# Teilentwurf.net
KiCad netlist of a schematic drawn in EAGLE
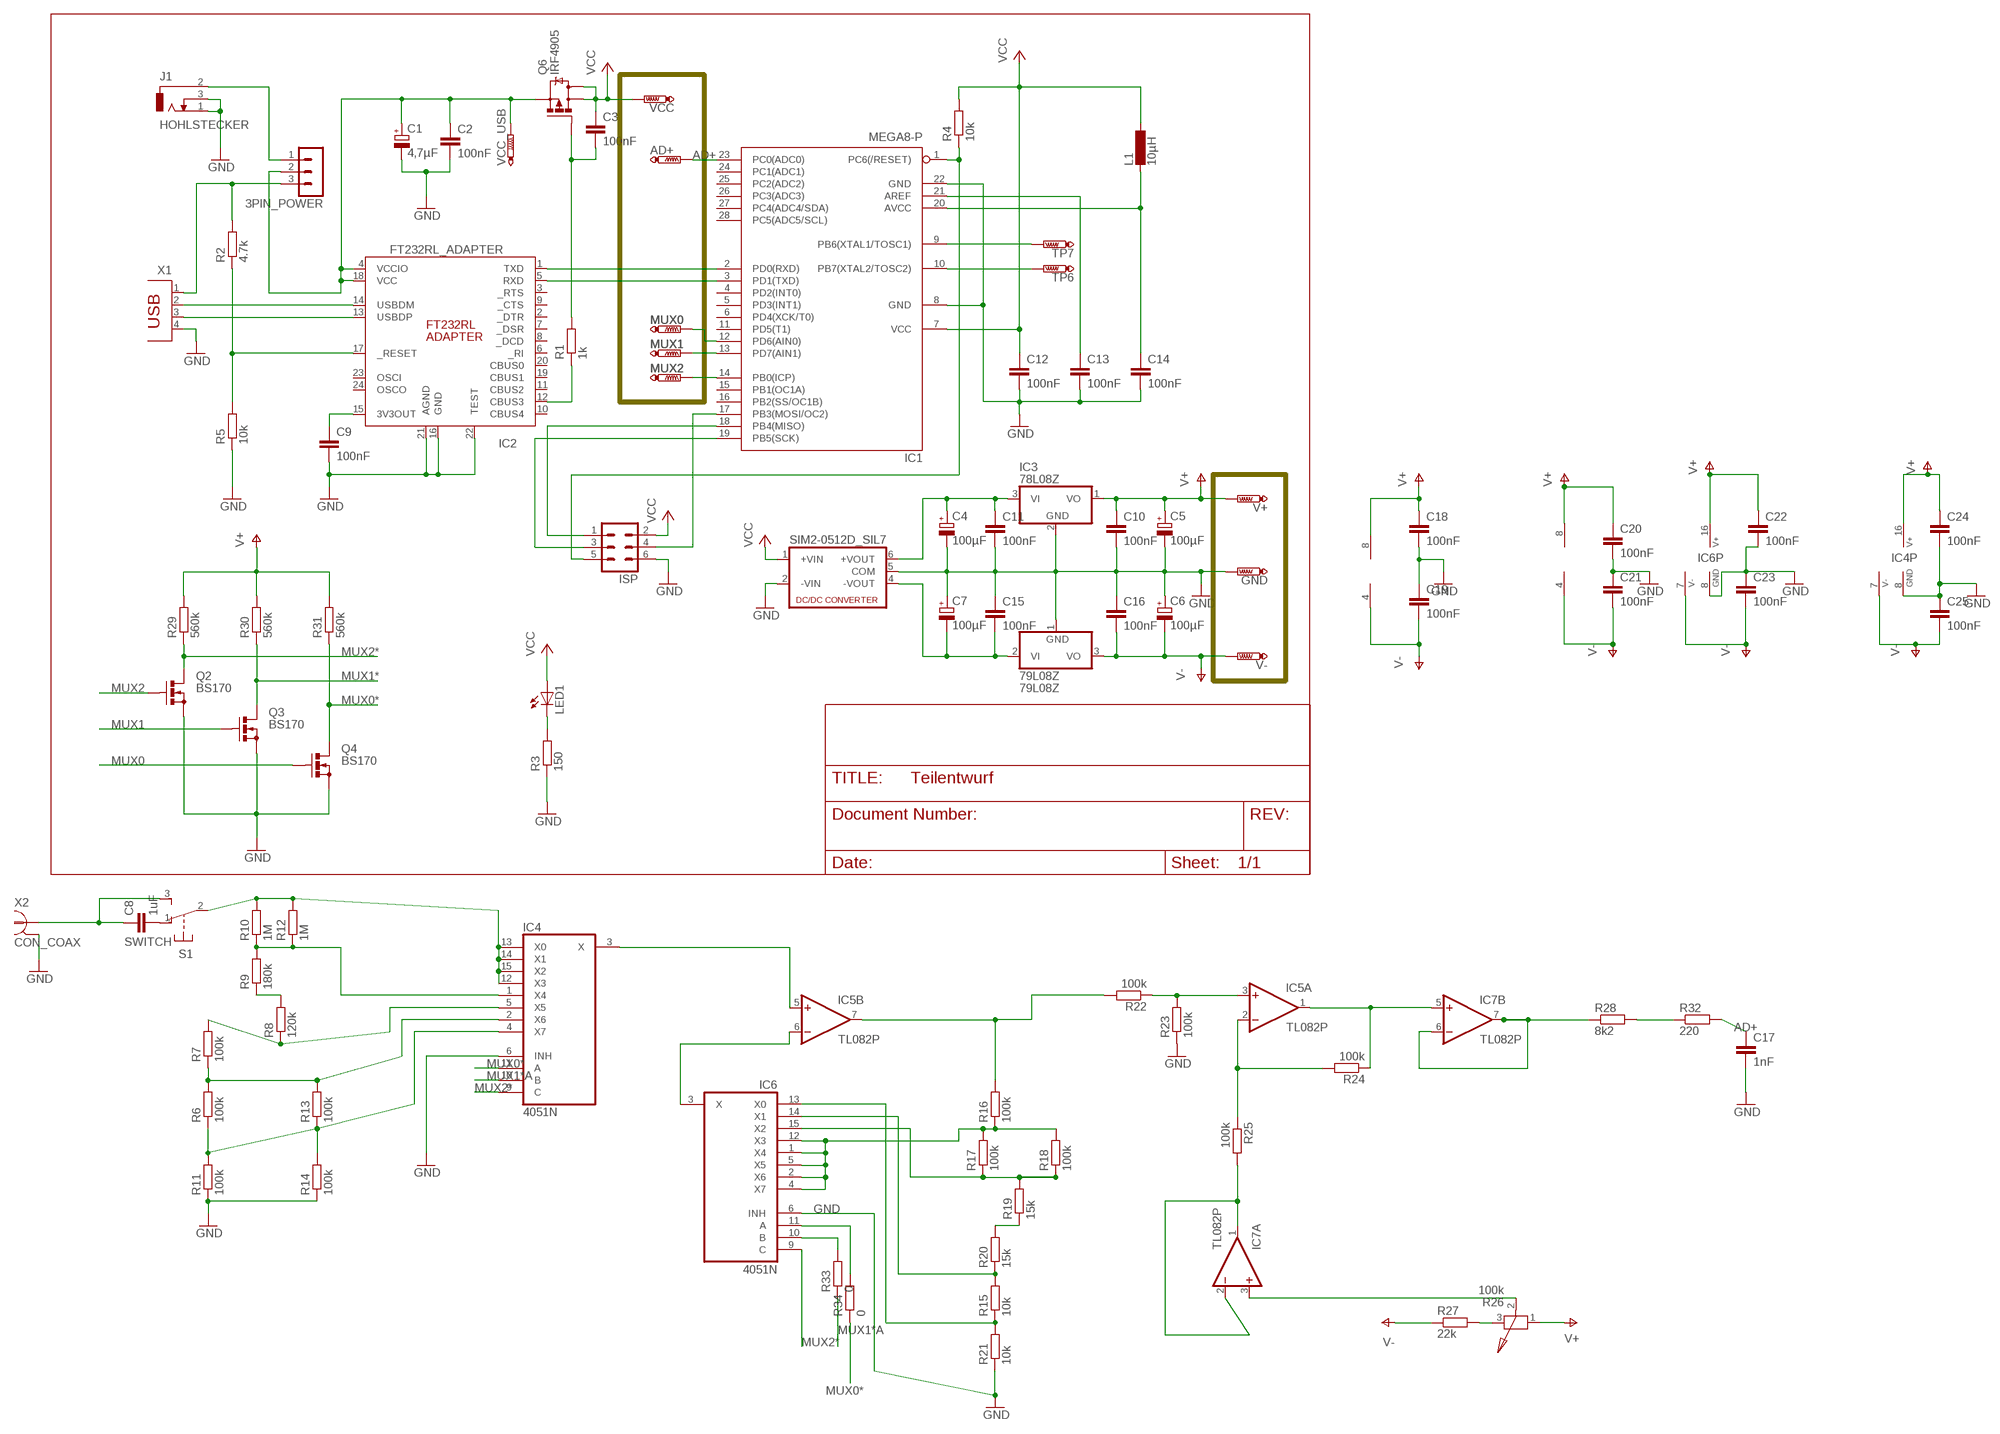
[diagram p0: schematic, sheet 1]

(export (version "E")
  (design (tool "Eeschema 10.0.6"))
  (components
    (comp (ref "3PIN_POWER")
      (value "MA03-1")
      (footprint "eagle-import:MA03-1")
      (libsource (lib "eagle-import") (part "MA03-1"))
    )
    (comp (ref "79L08Z")
      (value "79L08Z")
      (footprint "eagle-import:TO92")
      (libsource (lib "eagle-import") (part "79ZL08"))
    )
    (comp (ref "AD+")
      (value "PTR1PAD1-13Y")
      (footprint "eagle-import:P1-13Y")
      (libsource (lib "eagle-import") (part "PTR1PAD1-13Y"))
    )
    (comp (ref "C1")
      (value "4,7µF")
      (footprint "eagle-import:E2-5")
      (libsource (lib "eagle-import") (part "CPOL-EUE2-5"))
    )
    (comp (ref "C2")
      (value "100nF")
      (footprint "eagle-import:C025-030X050")
      (libsource (lib "eagle-import") (part "C-EU025-030X050"))
    )
    (comp (ref "C3")
      (value "100nF")
      (footprint "eagle-import:C025-030X050")
      (libsource (lib "eagle-import") (part "C-EU025-030X050"))
    )
    (comp (ref "C4")
      (value "100µF")
      (footprint "eagle-import:E2,5-7")
      (libsource (lib "eagle-import") (part "CPOL-EUE2.5-7"))
    )
    (comp (ref "C5")
      (value "100µF")
      (footprint "eagle-import:E2,5-7")
      (libsource (lib "eagle-import") (part "CPOL-EUE2.5-7"))
    )
    (comp (ref "C6")
      (value "100µF")
      (footprint "eagle-import:E2,5-7")
      (libsource (lib "eagle-import") (part "CPOL-EUE2.5-7"))
    )
    (comp (ref "C7")
      (value "100µF")
      (footprint "eagle-import:E2,5-7")
      (libsource (lib "eagle-import") (part "CPOL-EUE2.5-7"))
    )
    (comp (ref "C8")
      (value "1uF")
      (footprint "eagle-import:C050-050X075")
      (libsource (lib "eagle-import") (part "C-EU050-050X075"))
    )
    (comp (ref "C9")
      (value "100nF")
      (footprint "eagle-import:C025-030X050")
      (libsource (lib "eagle-import") (part "C-EU025-030X050"))
    )
    (comp (ref "C10")
      (value "100nF")
      (footprint "eagle-import:C025-030X050")
      (libsource (lib "eagle-import") (part "C-EU025-030X050"))
    )
    (comp (ref "C11")
      (value "100nF")
      (footprint "eagle-import:C025-030X050")
      (libsource (lib "eagle-import") (part "C-EU025-030X050"))
    )
    (comp (ref "C12")
      (value "100nF")
      (footprint "eagle-import:C025-030X050")
      (libsource (lib "eagle-import") (part "C-EU025-030X050"))
    )
    (comp (ref "C13")
      (value "100nF")
      (footprint "eagle-import:C025-030X050")
      (libsource (lib "eagle-import") (part "C-EU025-030X050"))
    )
    (comp (ref "C14")
      (value "100nF")
      (footprint "eagle-import:C025-030X050")
      (libsource (lib "eagle-import") (part "C-EU025-030X050"))
    )
    (comp (ref "C15")
      (value "100nF")
      (footprint "eagle-import:C025-030X050")
      (libsource (lib "eagle-import") (part "C-EU025-030X050"))
    )
    (comp (ref "C16")
      (value "100nF")
      (footprint "eagle-import:C025-030X050")
      (libsource (lib "eagle-import") (part "C-EU025-030X050"))
    )
    (comp (ref "C17")
      (value "1nF")
      (footprint "eagle-import:C025-030X050")
      (libsource (lib "eagle-import") (part "C-EU025-030X050"))
    )
    (comp (ref "C18")
      (value "100nF")
      (footprint "eagle-import:C025-030X050")
      (libsource (lib "eagle-import") (part "C-EU025-030X050"))
    )
    (comp (ref "C19")
      (value "100nF")
      (footprint "eagle-import:C025-030X050")
      (libsource (lib "eagle-import") (part "C-EU025-030X050"))
    )
    (comp (ref "C20")
      (value "100nF")
      (footprint "eagle-import:C025-030X050")
      (libsource (lib "eagle-import") (part "C-EU025-030X050"))
    )
    (comp (ref "C21")
      (value "100nF")
      (footprint "eagle-import:C025-030X050")
      (libsource (lib "eagle-import") (part "C-EU025-030X050"))
    )
    (comp (ref "C22")
      (value "100nF")
      (footprint "eagle-import:C025-030X050")
      (libsource (lib "eagle-import") (part "C-EU025-030X050"))
    )
    (comp (ref "C23")
      (value "100nF")
      (footprint "eagle-import:C025-030X050")
      (libsource (lib "eagle-import") (part "C-EU025-030X050"))
    )
    (comp (ref "C24")
      (value "100nF")
      (footprint "eagle-import:C025-030X050")
      (libsource (lib "eagle-import") (part "C-EU025-030X050"))
    )
    (comp (ref "C25")
      (value "100nF")
      (footprint "eagle-import:C025-030X050")
      (libsource (lib "eagle-import") (part "C-EU025-030X050"))
    )
    (comp (ref "GND")
      (value "PTR1PAD1-13Y")
      (footprint "eagle-import:P1-13Y")
      (libsource (lib "eagle-import") (part "PTR1PAD1-13Y"))
    )
    (comp (ref "IC1")
      (value "MEGA8-P")
      (footprint "eagle-import:DIL28-3")
      (libsource (lib "eagle-import") (part "MEGA8-P"))
    )
    (comp (ref "IC2")
      (value "FT232RL_ADAPTER")
      (footprint "eagle-import:DIL24-9")
      (libsource (lib "eagle-import") (part "FT232RL_ADAPTER"))
    )
    (comp (ref "IC3")
      (value "78L08Z")
      (footprint "eagle-import:TO92")
      (libsource (lib "eagle-import") (part "78ZL08"))
    )
    (comp (ref "IC4")
      (value "4051N")
      (footprint "eagle-import:DIL16")
      (libsource (lib "eagle-import") (part "4051N"))
    )
    (comp (ref "IC5")
      (value "TL082P")
      (footprint "eagle-import:DIL08")
      (libsource (lib "eagle-import") (part "TL082P"))
    )
    (comp (ref "IC6")
      (value "4051N")
      (footprint "eagle-import:DIL16")
      (libsource (lib "eagle-import") (part "4051N"))
    )
    (comp (ref "IC7")
      (value "TL082P")
      (footprint "eagle-import:DIL08")
      (libsource (lib "eagle-import") (part "TL082P"))
    )
    (comp (ref "ISP")
      (value "ML6")
      (footprint "eagle-import:ML6")
      (libsource (lib "eagle-import") (part "ML6"))
    )
    (comp (ref "J1")
      (value "HOHLSTECKER")
      (footprint "eagle-import:HOHLSTECKER_25")
      (libsource (lib "eagle-import") (part "HOHLSTECKER"))
    )
    (comp (ref "L1")
      (value "10µH")
      (footprint "eagle-import:0207_12")
      (libsource (lib "eagle-import") (part "L-EU0207/12"))
    )
    (comp (ref "LED1")
      (value "LED3MM")
      (footprint "eagle-import:LED3MM")
      (libsource (lib "eagle-import") (part "LED3MM"))
    )
    (comp (ref "MUX0")
      (value "PTR1PAD1-13Y")
      (footprint "eagle-import:P1-13Y")
      (libsource (lib "eagle-import") (part "PTR1PAD1-13Y"))
    )
    (comp (ref "MUX1")
      (value "PTR1PAD1-13Y")
      (footprint "eagle-import:P1-13Y")
      (libsource (lib "eagle-import") (part "PTR1PAD1-13Y"))
    )
    (comp (ref "MUX2")
      (value "PTR1PAD1-13Y")
      (footprint "eagle-import:P1-13Y")
      (libsource (lib "eagle-import") (part "PTR1PAD1-13Y"))
    )
    (comp (ref "Q2")
      (value "BS170")
      (footprint "eagle-import:SOT54E")
      (libsource (lib "eagle-import") (part "BS170"))
    )
    (comp (ref "Q3")
      (value "BS170")
      (footprint "eagle-import:SOT54E")
      (libsource (lib "eagle-import") (part "BS170"))
    )
    (comp (ref "Q4")
      (value "BS170")
      (footprint "eagle-import:SOT54E")
      (libsource (lib "eagle-import") (part "BS170"))
    )
    (comp (ref "Q6")
      (value "IRF4905")
      (footprint "eagle-import:TO220PAD")
      (libsource (lib "eagle-import") (part "IRF4905PBF"))
    )
    (comp (ref "R1")
      (value "1k")
      (footprint "eagle-import:0207_10")
      (libsource (lib "eagle-import") (part "R-EU_0207/10"))
    )
    (comp (ref "R2")
      (value "4.7k")
      (footprint "eagle-import:0207_10")
      (libsource (lib "eagle-import") (part "R-EU_0207/10"))
    )
    (comp (ref "R3")
      (value "150")
      (footprint "eagle-import:0207_10")
      (libsource (lib "eagle-import") (part "R-EU_0207/10"))
    )
    (comp (ref "R4")
      (value "10k")
      (footprint "eagle-import:0207_12")
      (libsource (lib "eagle-import") (part "R-EU_0207/12"))
    )
    (comp (ref "R5")
      (value "10k")
      (footprint "eagle-import:0207_10")
      (libsource (lib "eagle-import") (part "R-EU_0207/10"))
    )
    (comp (ref "R6")
      (value "100k")
      (footprint "eagle-import:0207_10")
      (libsource (lib "eagle-import") (part "R-EU_0207/10"))
    )
    (comp (ref "R7")
      (value "100k")
      (footprint "eagle-import:0207_10")
      (libsource (lib "eagle-import") (part "R-EU_0207/10"))
    )
    (comp (ref "R8")
      (value "120k")
      (footprint "eagle-import:0207_10")
      (libsource (lib "eagle-import") (part "R-EU_0207/10"))
    )
    (comp (ref "R9")
      (value "180k")
      (footprint "eagle-import:0207_10")
      (libsource (lib "eagle-import") (part "R-EU_0207/10"))
    )
    (comp (ref "R10")
      (value "1M")
      (footprint "eagle-import:0207_10")
      (libsource (lib "eagle-import") (part "R-EU_0207/10"))
    )
    (comp (ref "R11")
      (value "100k")
      (footprint "eagle-import:0207_10")
      (libsource (lib "eagle-import") (part "R-EU_0207/10"))
    )
    (comp (ref "R12")
      (value "1M")
      (footprint "eagle-import:0207_10")
      (libsource (lib "eagle-import") (part "R-EU_0207/10"))
    )
    (comp (ref "R13")
      (value "100k")
      (footprint "eagle-import:0207_10")
      (libsource (lib "eagle-import") (part "R-EU_0207/10"))
    )
    (comp (ref "R14")
      (value "100k")
      (footprint "eagle-import:0207_10")
      (libsource (lib "eagle-import") (part "R-EU_0207/10"))
    )
    (comp (ref "R15")
      (value "10k")
      (footprint "eagle-import:0207_10")
      (libsource (lib "eagle-import") (part "R-EU_0207/10"))
    )
    (comp (ref "R16")
      (value "100k")
      (footprint "eagle-import:0207_10")
      (libsource (lib "eagle-import") (part "R-EU_0207/10"))
    )
    (comp (ref "R17")
      (value "100k")
      (footprint "eagle-import:0207_10")
      (libsource (lib "eagle-import") (part "R-EU_0207/10"))
    )
    (comp (ref "R18")
      (value "100k")
      (footprint "eagle-import:0207_10")
      (libsource (lib "eagle-import") (part "R-EU_0207/10"))
    )
    (comp (ref "R19")
      (value "15k")
      (footprint "eagle-import:0207_10")
      (libsource (lib "eagle-import") (part "R-EU_0207/10"))
    )
    (comp (ref "R20")
      (value "15k")
      (footprint "eagle-import:0207_10")
      (libsource (lib "eagle-import") (part "R-EU_0207/10"))
    )
    (comp (ref "R21")
      (value "10k")
      (footprint "eagle-import:0207_10")
      (libsource (lib "eagle-import") (part "R-EU_0207/10"))
    )
    (comp (ref "R22")
      (value "100k")
      (footprint "eagle-import:0207_10")
      (libsource (lib "eagle-import") (part "R-EU_0207/10"))
    )
    (comp (ref "R23")
      (value "100k")
      (footprint "eagle-import:0207_10")
      (libsource (lib "eagle-import") (part "R-EU_0207/10"))
    )
    (comp (ref "R24")
      (value "100k")
      (footprint "eagle-import:0207_10")
      (libsource (lib "eagle-import") (part "R-EU_0207/10"))
    )
    (comp (ref "R25")
      (value "100k")
      (footprint "eagle-import:0207_7")
      (libsource (lib "eagle-import") (part "R-EU_0207/7"))
    )
    (comp (ref "R26")
      (value "100k")
      (footprint "eagle-import:POT")
      (libsource (lib "eagle-import") (part "POT"))
    )
    (comp (ref "R27")
      (value "22k")
      (footprint "eagle-import:0207_10")
      (libsource (lib "eagle-import") (part "R-EU_0207/10"))
    )
    (comp (ref "R28")
      (value "8k2")
      (footprint "eagle-import:0207_10")
      (libsource (lib "eagle-import") (part "R-EU_0207/10"))
    )
    (comp (ref "R29")
      (value "560k")
      (footprint "eagle-import:0207_10")
      (libsource (lib "eagle-import") (part "R-EU_0207/10"))
    )
    (comp (ref "R30")
      (value "560k")
      (footprint "eagle-import:0207_10")
      (libsource (lib "eagle-import") (part "R-EU_0207/10"))
    )
    (comp (ref "R31")
      (value "560k")
      (footprint "eagle-import:0207_10")
      (libsource (lib "eagle-import") (part "R-EU_0207/10"))
    )
    (comp (ref "R32")
      (value "220")
      (footprint "eagle-import:0207_15")
      (libsource (lib "eagle-import") (part "R-EU_0207/15"))
    )
    (comp (ref "R33")
      (value "0")
      (footprint "eagle-import:0207_10")
      (libsource (lib "eagle-import") (part "R-EU_0207/10"))
    )
    (comp (ref "R34")
      (value "0")
      (footprint "eagle-import:0207_10")
      (libsource (lib "eagle-import") (part "R-EU_0207/10"))
    )
    (comp (ref "S1")
      (value "SWITCH")
      (footprint "eagle-import:APEM_5236")
      (libsource (lib "eagle-import") (part "SWITCH"))
    )
    (comp (ref "SIM2-0512D_SIL7")
      (value "NMA")
      (footprint "eagle-import:NMA")
      (libsource (lib "eagle-import") (part "NMA"))
    )
    (comp (ref "TP6")
      (value "PTR1PAD1-13Y")
      (footprint "eagle-import:P1-13Y")
      (libsource (lib "eagle-import") (part "PTR1PAD1-13Y"))
    )
    (comp (ref "TP7")
      (value "PTR1PAD1-13Y")
      (footprint "eagle-import:P1-13Y")
      (libsource (lib "eagle-import") (part "PTR1PAD1-13Y"))
    )
    (comp (ref "V+")
      (value "PTR1PAD1-13Y")
      (footprint "eagle-import:P1-13Y")
      (libsource (lib "eagle-import") (part "PTR1PAD1-13Y"))
    )
    (comp (ref "V-")
      (value "PTR1PAD1-13Y")
      (footprint "eagle-import:P1-13Y")
      (libsource (lib "eagle-import") (part "PTR1PAD1-13Y"))
    )
    (comp (ref "VCC")
      (value "PTR1PAD1-13Y")
      (footprint "eagle-import:P1-13Y")
      (libsource (lib "eagle-import") (part "PTR1PAD1-13Y"))
    )
    (comp (ref "VCC_USB")
      (value "PTR1PAD1-13Y")
      (footprint "eagle-import:P1-13Y")
      (libsource (lib "eagle-import") (part "PTR1PAD1-13Y"))
    )
    (comp (ref "X1")
      (value "USB_BUCHSE_B")
      (footprint "eagle-import:USB_BUCHSE_B")
      (libsource (lib "eagle-import") (part "USB_BUCHSE_B"))
    )
    (comp (ref "X2")
      (value "CON_COAX")
      (footprint "eagle-import:CON_COAX")
      (libsource (lib "eagle-import") (part "CON_COAX"))
    )
  )
  (nets
    (net (code "1") (name "/AD+") (class "Default")
      (node (ref "AD+") (pin "TP") (pinfunction "TP_TP") (pintype "input"))
      (node (ref "C17") (pin "1") (pinfunction "1_1") (pintype "passive"))
      (node (ref "IC1") (pin "23") (pinfunction "PC0(ADC0)_23") (pintype "bidirectional"))
      (node (ref "R32") (pin "2") (pinfunction "2_2") (pintype "passive"))
    )
    (net (code "2") (name "/MUX0") (class "Default")
      (node (ref "IC1") (pin "12") (pinfunction "PD6(AIN0)_12") (pintype "bidirectional"))
      (node (ref "MUX0") (pin "TP") (pinfunction "TP_TP") (pintype "input"))
      (node (ref "Q4") (pin "G") (pinfunction "G_G") (pintype "passive"))
    )
    (net (code "3") (name "/MUX0*") (class "Default")
      (node (ref "IC4") (pin "11") (pinfunction "A_11") (pintype "input"))
      (node (ref "Q4") (pin "D") (pinfunction "D_D") (pintype "passive"))
      (node (ref "R31") (pin "1") (pinfunction "1_1") (pintype "passive"))
      (node (ref "R34") (pin "1") (pinfunction "1_1") (pintype "passive"))
    )
    (net (code "4") (name "/MUX1") (class "Default")
      (node (ref "IC1") (pin "13") (pinfunction "PD7(AIN1)_13") (pintype "bidirectional"))
      (node (ref "MUX1") (pin "TP") (pinfunction "TP_TP") (pintype "input"))
      (node (ref "Q3") (pin "G") (pinfunction "G_G") (pintype "passive"))
    )
    (net (code "5") (name "/MUX1*") (class "Default")
      (node (ref "IC6") (pin "10") (pinfunction "B_10") (pintype "input"))
      (node (ref "Q3") (pin "D") (pinfunction "D_D") (pintype "passive"))
      (node (ref "R30") (pin "1") (pinfunction "1_1") (pintype "passive"))
      (node (ref "R33") (pin "2") (pinfunction "2_2") (pintype "passive"))
    )
    (net (code "6") (name "/MUX1*A") (class "Default")
      (node (ref "IC4") (pin "10") (pinfunction "B_10") (pintype "input"))
      (node (ref "R33") (pin "1") (pinfunction "1_1") (pintype "passive"))
    )
    (net (code "7") (name "/MUX2") (class "Default")
      (node (ref "IC1") (pin "14") (pinfunction "PB0(ICP)_14") (pintype "bidirectional"))
      (node (ref "MUX2") (pin "TP") (pinfunction "TP_TP") (pintype "input"))
      (node (ref "Q2") (pin "G") (pinfunction "G_G") (pintype "passive"))
    )
    (net (code "8") (name "/MUX2*") (class "Default")
      (node (ref "IC4") (pin "9") (pinfunction "C_9") (pintype "input"))
      (node (ref "IC6") (pin "9") (pinfunction "C_9") (pintype "input"))
      (node (ref "Q2") (pin "D") (pinfunction "D_D") (pintype "passive"))
      (node (ref "R29") (pin "1") (pinfunction "1_1") (pintype "passive"))
    )
    (net (code "9") (name "GND") (class "Default")
      (node (ref "79L08Z") (pin "1") (pinfunction "GND_1") (pintype "passive"))
      (node (ref "C1") (pin "-") (pinfunction "-_-") (pintype "passive"))
      (node (ref "C10") (pin "2") (pinfunction "2_2") (pintype "passive"))
      (node (ref "C11") (pin "2") (pinfunction "2_2") (pintype "passive"))
      (node (ref "C12") (pin "2") (pinfunction "2_2") (pintype "passive"))
      (node (ref "C13") (pin "2") (pinfunction "2_2") (pintype "passive"))
      (node (ref "C14") (pin "2") (pinfunction "2_2") (pintype "passive"))
      (node (ref "C15") (pin "1") (pinfunction "1_1") (pintype "passive"))
      (node (ref "C16") (pin "1") (pinfunction "1_1") (pintype "passive"))
      (node (ref "C17") (pin "2") (pinfunction "2_2") (pintype "passive"))
      (node (ref "C18") (pin "2") (pinfunction "2_2") (pintype "passive"))
      (node (ref "C19") (pin "1") (pinfunction "1_1") (pintype "passive"))
      (node (ref "C2") (pin "2") (pinfunction "2_2") (pintype "passive"))
      (node (ref "C20") (pin "2") (pinfunction "2_2") (pintype "passive"))
      (node (ref "C21") (pin "1") (pinfunction "1_1") (pintype "passive"))
      (node (ref "C22") (pin "2") (pinfunction "2_2") (pintype "passive"))
      (node (ref "C23") (pin "1") (pinfunction "1_1") (pintype "passive"))
      (node (ref "C24") (pin "2") (pinfunction "2_2") (pintype "passive"))
      (node (ref "C25") (pin "1") (pinfunction "1_1") (pintype "passive"))
      (node (ref "C4") (pin "-") (pinfunction "-_-") (pintype "passive"))
      (node (ref "C5") (pin "-") (pinfunction "-_-") (pintype "passive"))
      (node (ref "C6") (pin "+") (pinfunction "+_+") (pintype "passive"))
      (node (ref "C7") (pin "+") (pinfunction "+_+") (pintype "passive"))
      (node (ref "C9") (pin "2") (pinfunction "2_2") (pintype "passive"))
      (node (ref "GND") (pin "TP") (pinfunction "TP_TP") (pintype "input"))
      (node (ref "IC1") (pin "22") (pinfunction "GND_22") (pintype "power_in"))
      (node (ref "IC1") (pin "8") (pinfunction "GND_8") (pintype "power_in"))
      (node (ref "IC2") (pin "16") (pinfunction "GND_16") (pintype "power_in"))
      (node (ref "IC2") (pin "21") (pinfunction "AGND_21") (pintype "power_in"))
      (node (ref "IC2") (pin "22") (pinfunction "TEST_22") (pintype "bidirectional"))
      (node (ref "IC3") (pin "2") (pinfunction "GND_2") (pintype "passive"))
      (node (ref "IC4") (pin "6") (pinfunction "INH_6") (pintype "input"))
      (node (ref "IC4") (pin "8") (pinfunction "GND_8") (pintype "power_in"))
      (node (ref "IC6") (pin "6") (pinfunction "INH_6") (pintype "input"))
      (node (ref "IC6") (pin "8") (pinfunction "GND_8") (pintype "power_in"))
      (node (ref "ISP") (pin "6") (pinfunction "6_6") (pintype "passive"))
      (node (ref "J1") (pin "1") (pinfunction "3_1") (pintype "passive"))
      (node (ref "J1") (pin "3") (pinfunction "2_3") (pintype "passive"))
      (node (ref "Q2") (pin "S") (pinfunction "S_S") (pintype "passive"))
      (node (ref "Q3") (pin "S") (pinfunction "S_S") (pintype "passive"))
      (node (ref "Q4") (pin "S") (pinfunction "S_S") (pintype "passive"))
      (node (ref "R11") (pin "1") (pinfunction "1_1") (pintype "passive"))
      (node (ref "R14") (pin "1") (pinfunction "1_1") (pintype "passive"))
      (node (ref "R21") (pin "1") (pinfunction "1_1") (pintype "passive"))
      (node (ref "R23") (pin "1") (pinfunction "1_1") (pintype "passive"))
      (node (ref "R3") (pin "1") (pinfunction "1_1") (pintype "passive"))
      (node (ref "R5") (pin "1") (pinfunction "1_1") (pintype "passive"))
      (node (ref "SIM2-0512D_SIL7") (pin "2") (pinfunction "-VIN_2") (pintype "passive"))
      (node (ref "SIM2-0512D_SIL7") (pin "5") (pinfunction "COM_5") (pintype "passive"))
      (node (ref "X1") (pin "4") (pinfunction "4_4") (pintype "bidirectional"))
      (node (ref "X2") (pin "GND") (pinfunction "GND_GND") (pintype "power_in"))
    )
    (net (code "10") (name "Net-(3PIN_POWER-Pad3)") (class "Default")
      (node (ref "3PIN_POWER") (pin "3") (pinfunction "3_3") (pintype "passive"))
      (node (ref "R2") (pin "2") (pinfunction "2_2") (pintype "passive"))
      (node (ref "X1") (pin "1") (pinfunction "1_1") (pintype "bidirectional"))
    )
    (net (code "11") (name "Net-(79L08Z-VI)") (class "Default")
      (node (ref "79L08Z") (pin "2") (pinfunction "VI_2") (pintype "input"))
      (node (ref "C15") (pin "2") (pinfunction "2_2") (pintype "passive"))
      (node (ref "C7") (pin "-") (pinfunction "-_-") (pintype "passive"))
      (node (ref "SIM2-0512D_SIL7") (pin "4") (pinfunction "-VOUT_4") (pintype "passive"))
    )
    (net (code "12") (name "Net-(C3-Pad2)") (class "Default")
      (node (ref "C3") (pin "2") (pinfunction "2_2") (pintype "passive"))
      (node (ref "Q6") (pin "G") (pinfunction "G_G") (pintype "passive"))
      (node (ref "R1") (pin "2") (pinfunction "2_2") (pintype "passive"))
    )
    (net (code "13") (name "Net-(IC1-AREF)") (class "Default")
      (node (ref "C13") (pin "1") (pinfunction "1_1") (pintype "passive"))
      (node (ref "IC1") (pin "21") (pinfunction "AREF_21") (pintype "passive"))
    )
    (net (code "14") (name "Net-(IC1-AVCC)") (class "Default")
      (node (ref "C14") (pin "1") (pinfunction "1_1") (pintype "passive"))
      (node (ref "IC1") (pin "20") (pinfunction "AVCC_20") (pintype "power_in"))
      (node (ref "L1") (pin "2") (pinfunction "2_2") (pintype "passive"))
    )
    (net (code "15") (name "Net-(IC1-PB3(MOSI{slash}OC2))") (class "Default")
      (node (ref "IC1") (pin "17") (pinfunction "PB3(MOSI/OC2)_17") (pintype "bidirectional"))
      (node (ref "ISP") (pin "4") (pinfunction "4_4") (pintype "passive"))
    )
    (net (code "16") (name "Net-(IC1-PB4(MISO))") (class "Default")
      (node (ref "IC1") (pin "18") (pinfunction "PB4(MISO)_18") (pintype "bidirectional"))
      (node (ref "ISP") (pin "1") (pinfunction "1_1") (pintype "passive"))
    )
    (net (code "17") (name "Net-(IC1-PB5(SCK))") (class "Default")
      (node (ref "IC1") (pin "19") (pinfunction "PB5(SCK)_19") (pintype "bidirectional"))
      (node (ref "ISP") (pin "3") (pinfunction "3_3") (pintype "passive"))
    )
    (net (code "18") (name "Net-(IC1-PB6(XTAL1{slash}TOSC1))") (class "Default")
      (node (ref "IC1") (pin "9") (pinfunction "PB6(XTAL1/TOSC1)_9") (pintype "bidirectional"))
      (node (ref "TP7") (pin "TP") (pinfunction "TP_TP") (pintype "input"))
    )
    (net (code "19") (name "Net-(IC1-PB7(XTAL2{slash}TOSC2))") (class "Default")
      (node (ref "IC1") (pin "10") (pinfunction "PB7(XTAL2/TOSC2)_10") (pintype "bidirectional"))
      (node (ref "TP6") (pin "TP") (pinfunction "TP_TP") (pintype "input"))
    )
    (net (code "20") (name "Net-(IC1-PC6({slash}RESET))") (class "Default")
      (node (ref "IC1") (pin "1") (pinfunction "PC6(/RESET)_1") (pintype "bidirectional"))
      (node (ref "ISP") (pin "5") (pinfunction "5_5") (pintype "passive"))
      (node (ref "R4") (pin "1") (pinfunction "1_1") (pintype "passive"))
    )
    (net (code "21") (name "Net-(IC1-PD0(RXD))") (class "Default")
      (node (ref "IC1") (pin "2") (pinfunction "PD0(RXD)_2") (pintype "bidirectional"))
      (node (ref "IC2") (pin "1") (pinfunction "TXD_1") (pintype "output"))
    )
    (net (code "22") (name "Net-(IC1-PD1(TXD))") (class "Default")
      (node (ref "IC1") (pin "3") (pinfunction "PD1(TXD)_3") (pintype "bidirectional"))
      (node (ref "IC2") (pin "5") (pinfunction "RXD_5") (pintype "input"))
    )
    (net (code "23") (name "Net-(IC2-3V3OUT)") (class "Default")
      (node (ref "C9") (pin "1") (pinfunction "1_1") (pintype "passive"))
      (node (ref "IC2") (pin "15") (pinfunction "3V3OUT_15") (pintype "output"))
    )
    (net (code "24") (name "Net-(IC2-CBUS3)") (class "Default")
      (node (ref "IC2") (pin "12") (pinfunction "CBUS3_12") (pintype "bidirectional"))
      (node (ref "R1") (pin "1") (pinfunction "1_1") (pintype "passive"))
    )
    (net (code "25") (name "Net-(IC2-USBDM)") (class "Default")
      (node (ref "IC2") (pin "14") (pinfunction "USBDM_14") (pintype "bidirectional"))
      (node (ref "X1") (pin "2") (pinfunction "2_2") (pintype "bidirectional"))
    )
    (net (code "26") (name "Net-(IC2-USBDP)") (class "Default")
      (node (ref "IC2") (pin "13") (pinfunction "USBDP_13") (pintype "bidirectional"))
      (node (ref "X1") (pin "3") (pinfunction "3_3") (pintype "bidirectional"))
    )
    (net (code "27") (name "Net-(IC2-VCC)") (class "Default")
      (node (ref "3PIN_POWER") (pin "2") (pinfunction "2_2") (pintype "passive"))
      (node (ref "C1") (pin "+") (pinfunction "+_+") (pintype "passive"))
      (node (ref "C2") (pin "1") (pinfunction "1_1") (pintype "passive"))
      (node (ref "IC2") (pin "18") (pinfunction "VCC_18") (pintype "power_in"))
      (node (ref "IC2") (pin "4") (pinfunction "VCCIO_4") (pintype "power_in"))
      (node (ref "Q6") (pin "S") (pinfunction "S_S") (pintype "passive"))
      (node (ref "VCC_USB") (pin "TP") (pinfunction "TP_TP") (pintype "input"))
    )
    (net (code "28") (name "Net-(IC2-_RESET)") (class "Default")
      (node (ref "IC2") (pin "17") (pinfunction "_RESET_17") (pintype "input"))
      (node (ref "R2") (pin "1") (pinfunction "1_1") (pintype "passive"))
      (node (ref "R5") (pin "2") (pinfunction "2_2") (pintype "passive"))
    )
    (net (code "29") (name "Net-(IC3-VI)") (class "Default")
      (node (ref "C11") (pin "1") (pinfunction "1_1") (pintype "passive"))
      (node (ref "C4") (pin "+") (pinfunction "+_+") (pintype "passive"))
      (node (ref "IC3") (pin "3") (pinfunction "VI_3") (pintype "input"))
      (node (ref "SIM2-0512D_SIL7") (pin "6") (pinfunction "+VOUT_6") (pintype "passive"))
    )
    (net (code "30") (name "Net-(IC4A-X)") (class "Default")
      (node (ref "IC4") (pin "3") (pinfunction "X_3") (pintype "bidirectional"))
      (node (ref "IC5") (pin "5") (pinfunction "+IN_5") (pintype "input"))
    )
    (net (code "31") (name "Net-(IC4A-X0)") (class "Default")
      (node (ref "IC4") (pin "12") (pinfunction "X3_12") (pintype "bidirectional"))
      (node (ref "IC4") (pin "13") (pinfunction "X0_13") (pintype "bidirectional"))
      (node (ref "IC4") (pin "14") (pinfunction "X1_14") (pintype "bidirectional"))
      (node (ref "IC4") (pin "15") (pinfunction "X2_15") (pintype "bidirectional"))
      (node (ref "R10") (pin "2") (pinfunction "2_2") (pintype "passive"))
      (node (ref "R12") (pin "2") (pinfunction "2_2") (pintype "passive"))
      (node (ref "S1") (pin "2") (pinfunction "P_2") (pintype "passive"))
    )
    (net (code "32") (name "Net-(IC4A-X4)") (class "Default")
      (node (ref "IC4") (pin "1") (pinfunction "X4_1") (pintype "bidirectional"))
      (node (ref "R10") (pin "1") (pinfunction "1_1") (pintype "passive"))
      (node (ref "R12") (pin "1") (pinfunction "1_1") (pintype "passive"))
      (node (ref "R9") (pin "2") (pinfunction "2_2") (pintype "passive"))
    )
    (net (code "33") (name "Net-(IC4A-X5)") (class "Default")
      (node (ref "IC4") (pin "5") (pinfunction "X5_5") (pintype "bidirectional"))
      (node (ref "R7") (pin "2") (pinfunction "2_2") (pintype "passive"))
      (node (ref "R8") (pin "1") (pinfunction "1_1") (pintype "passive"))
    )
    (net (code "34") (name "Net-(IC4A-X6)") (class "Default")
      (node (ref "IC4") (pin "2") (pinfunction "X6_2") (pintype "bidirectional"))
      (node (ref "R13") (pin "2") (pinfunction "2_2") (pintype "passive"))
      (node (ref "R6") (pin "2") (pinfunction "2_2") (pintype "passive"))
      (node (ref "R7") (pin "1") (pinfunction "1_1") (pintype "passive"))
    )
    (net (code "35") (name "Net-(IC4A-X7)") (class "Default")
      (node (ref "IC4") (pin "4") (pinfunction "X7_4") (pintype "bidirectional"))
      (node (ref "R11") (pin "2") (pinfunction "2_2") (pintype "passive"))
      (node (ref "R13") (pin "1") (pinfunction "1_1") (pintype "passive"))
      (node (ref "R14") (pin "2") (pinfunction "2_2") (pintype "passive"))
      (node (ref "R6") (pin "1") (pinfunction "1_1") (pintype "passive"))
    )
    (net (code "36") (name "Net-(IC5A-+IN)") (class "Default")
      (node (ref "IC5") (pin "3") (pinfunction "+IN_3") (pintype "input"))
      (node (ref "R22") (pin "1") (pinfunction "1_1") (pintype "passive"))
      (node (ref "R23") (pin "2") (pinfunction "2_2") (pintype "passive"))
    )
    (net (code "37") (name "Net-(IC5A--IN)") (class "Default")
      (node (ref "IC5") (pin "2") (pinfunction "-IN_2") (pintype "input"))
      (node (ref "R24") (pin "2") (pinfunction "2_2") (pintype "passive"))
      (node (ref "R25") (pin "1") (pinfunction "1_1") (pintype "passive"))
    )
    (net (code "38") (name "Net-(IC5A-OUT)") (class "Default")
      (node (ref "IC5") (pin "1") (pinfunction "OUT_1") (pintype "output"))
      (node (ref "IC7") (pin "5") (pinfunction "+IN_5") (pintype "input"))
      (node (ref "R24") (pin "1") (pinfunction "1_1") (pintype "passive"))
    )
    (net (code "39") (name "Net-(IC5B--IN)") (class "Default")
      (node (ref "IC5") (pin "6") (pinfunction "-IN_6") (pintype "input"))
      (node (ref "IC6") (pin "3") (pinfunction "X_3") (pintype "bidirectional"))
    )
    (net (code "40") (name "Net-(IC5B-OUT)") (class "Default")
      (node (ref "IC5") (pin "7") (pinfunction "OUT_7") (pintype "output"))
      (node (ref "R16") (pin "2") (pinfunction "2_2") (pintype "passive"))
      (node (ref "R22") (pin "2") (pinfunction "2_2") (pintype "passive"))
    )
    (net (code "41") (name "Net-(IC6A-A)") (class "Default")
      (node (ref "IC6") (pin "11") (pinfunction "A_11") (pintype "input"))
      (node (ref "R34") (pin "2") (pinfunction "2_2") (pintype "passive"))
    )
    (net (code "42") (name "Net-(IC6A-X0)") (class "Default")
      (node (ref "IC6") (pin "13") (pinfunction "X0_13") (pintype "bidirectional"))
      (node (ref "R15") (pin "1") (pinfunction "1_1") (pintype "passive"))
      (node (ref "R21") (pin "2") (pinfunction "2_2") (pintype "passive"))
    )
    (net (code "43") (name "Net-(IC6A-X1)") (class "Default")
      (node (ref "IC6") (pin "14") (pinfunction "X1_14") (pintype "bidirectional"))
      (node (ref "R15") (pin "2") (pinfunction "2_2") (pintype "passive"))
      (node (ref "R20") (pin "1") (pinfunction "1_1") (pintype "passive"))
    )
    (net (code "44") (name "Net-(IC6A-X2)") (class "Default")
      (node (ref "IC6") (pin "15") (pinfunction "X2_15") (pintype "bidirectional"))
      (node (ref "R17") (pin "1") (pinfunction "1_1") (pintype "passive"))
      (node (ref "R18") (pin "1") (pinfunction "1_1") (pintype "passive"))
      (node (ref "R19") (pin "2") (pinfunction "2_2") (pintype "passive"))
    )
    (net (code "45") (name "Net-(IC6A-X3)") (class "Default")
      (node (ref "IC6") (pin "1") (pinfunction "X4_1") (pintype "bidirectional"))
      (node (ref "IC6") (pin "12") (pinfunction "X3_12") (pintype "bidirectional"))
      (node (ref "IC6") (pin "2") (pinfunction "X6_2") (pintype "bidirectional"))
      (node (ref "IC6") (pin "4") (pinfunction "X7_4") (pintype "bidirectional"))
      (node (ref "IC6") (pin "5") (pinfunction "X5_5") (pintype "bidirectional"))
      (node (ref "R16") (pin "1") (pinfunction "1_1") (pintype "passive"))
      (node (ref "R17") (pin "2") (pinfunction "2_2") (pintype "passive"))
      (node (ref "R18") (pin "2") (pinfunction "2_2") (pintype "passive"))
    )
    (net (code "46") (name "Net-(IC7A-+IN)") (class "Default")
      (node (ref "IC7") (pin "3") (pinfunction "+IN_3") (pintype "input"))
      (node (ref "R26") (pin "2") (pinfunction "3_2") (pintype "passive"))
    )
    (net (code "47") (name "Net-(IC7A--IN)") (class "Default")
      (node (ref "IC7") (pin "1") (pinfunction "OUT_1") (pintype "output"))
      (node (ref "IC7") (pin "2") (pinfunction "-IN_2") (pintype "input"))
      (node (ref "R25") (pin "2") (pinfunction "2_2") (pintype "passive"))
    )
    (net (code "48") (name "Net-(IC7B--IN)") (class "Default")
      (node (ref "IC7") (pin "6") (pinfunction "-IN_6") (pintype "input"))
      (node (ref "IC7") (pin "7") (pinfunction "OUT_7") (pintype "output"))
      (node (ref "R28") (pin "1") (pinfunction "1_1") (pintype "passive"))
    )
    (net (code "49") (name "Net-(J1-1)") (class "Default")
      (node (ref "3PIN_POWER") (pin "1") (pinfunction "1_1") (pintype "passive"))
      (node (ref "J1") (pin "2") (pinfunction "1_2") (pintype "passive"))
    )
    (net (code "50") (name "Net-(LED1-C)") (class "Default")
      (node (ref "LED1") (pin "K") (pinfunction "C_K") (pintype "passive"))
      (node (ref "R3") (pin "2") (pinfunction "2_2") (pintype "passive"))
    )
    (net (code "51") (name "Net-(R8-Pad2)") (class "Default")
      (node (ref "R8") (pin "2") (pinfunction "2_2") (pintype "passive"))
      (node (ref "R9") (pin "1") (pinfunction "1_1") (pintype "passive"))
    )
    (net (code "52") (name "Net-(R19-Pad1)") (class "Default")
      (node (ref "R19") (pin "1") (pinfunction "1_1") (pintype "passive"))
      (node (ref "R20") (pin "2") (pinfunction "2_2") (pintype "passive"))
    )
    (net (code "53") (name "Net-(R26-2)") (class "Default")
      (node (ref "R26") (pin "3") (pinfunction "2_3") (pintype "passive"))
      (node (ref "R27") (pin "2") (pinfunction "2_2") (pintype "passive"))
    )
    (net (code "54") (name "Net-(R28-Pad2)") (class "Default")
      (node (ref "R28") (pin "2") (pinfunction "2_2") (pintype "passive"))
      (node (ref "R32") (pin "1") (pinfunction "1_1") (pintype "passive"))
    )
    (net (code "55") (name "Net-(S1-O)") (class "Default")
      (node (ref "C8") (pin "2") (pinfunction "2_2") (pintype "passive"))
      (node (ref "S1") (pin "1") (pinfunction "O_1") (pintype "passive"))
    )
    (net (code "56") (name "Net-(S1-S)") (class "Default")
      (node (ref "C8") (pin "1") (pinfunction "1_1") (pintype "passive"))
      (node (ref "S1") (pin "3") (pinfunction "S_3") (pintype "passive"))
      (node (ref "X2") (pin "1") (pinfunction "1_1") (pintype "passive"))
    )
    (net (code "57") (name "V+") (class "Default")
      (node (ref "C10") (pin "1") (pinfunction "1_1") (pintype "passive"))
      (node (ref "C18") (pin "1") (pinfunction "1_1") (pintype "passive"))
      (node (ref "C20") (pin "1") (pinfunction "1_1") (pintype "passive"))
      (node (ref "C22") (pin "1") (pinfunction "1_1") (pintype "passive"))
      (node (ref "C24") (pin "1") (pinfunction "1_1") (pintype "passive"))
      (node (ref "C5") (pin "+") (pinfunction "+_+") (pintype "passive"))
      (node (ref "IC3") (pin "1") (pinfunction "VO_1") (pintype "passive"))
      (node (ref "IC4") (pin "16") (pinfunction "V+_16") (pintype "power_in"))
      (node (ref "IC5") (pin "8") (pinfunction "V+_8") (pintype "power_in"))
      (node (ref "IC6") (pin "16") (pinfunction "V+_16") (pintype "power_in"))
      (node (ref "IC7") (pin "8") (pinfunction "V+_8") (pintype "power_in"))
      (node (ref "R26") (pin "1") (pinfunction "1_1") (pintype "passive"))
      (node (ref "R29") (pin "2") (pinfunction "2_2") (pintype "passive"))
      (node (ref "R30") (pin "2") (pinfunction "2_2") (pintype "passive"))
      (node (ref "R31") (pin "2") (pinfunction "2_2") (pintype "passive"))
      (node (ref "V+") (pin "TP") (pinfunction "TP_TP") (pintype "input"))
    )
    (net (code "58") (name "V-") (class "Default")
      (node (ref "79L08Z") (pin "3") (pinfunction "VO_3") (pintype "passive"))
      (node (ref "C16") (pin "2") (pinfunction "2_2") (pintype "passive"))
      (node (ref "C19") (pin "2") (pinfunction "2_2") (pintype "passive"))
      (node (ref "C21") (pin "2") (pinfunction "2_2") (pintype "passive"))
      (node (ref "C23") (pin "2") (pinfunction "2_2") (pintype "passive"))
      (node (ref "C25") (pin "2") (pinfunction "2_2") (pintype "passive"))
      (node (ref "C6") (pin "-") (pinfunction "-_-") (pintype "passive"))
      (node (ref "IC4") (pin "7") (pinfunction "V-_7") (pintype "power_in"))
      (node (ref "IC5") (pin "4") (pinfunction "V-_4") (pintype "power_in"))
      (node (ref "IC6") (pin "7") (pinfunction "V-_7") (pintype "power_in"))
      (node (ref "IC7") (pin "4") (pinfunction "V-_4") (pintype "power_in"))
      (node (ref "R27") (pin "1") (pinfunction "1_1") (pintype "passive"))
      (node (ref "V-") (pin "TP") (pinfunction "TP_TP") (pintype "input"))
    )
    (net (code "59") (name "VCC") (class "Default")
      (node (ref "C12") (pin "1") (pinfunction "1_1") (pintype "passive"))
      (node (ref "C3") (pin "1") (pinfunction "1_1") (pintype "passive"))
      (node (ref "IC1") (pin "7") (pinfunction "VCC_7") (pintype "power_in"))
      (node (ref "ISP") (pin "2") (pinfunction "2_2") (pintype "passive"))
      (node (ref "L1") (pin "1") (pinfunction "1_1") (pintype "passive"))
      (node (ref "LED1") (pin "A") (pinfunction "A_A") (pintype "passive"))
      (node (ref "Q6") (pin "D") (pinfunction "D_D") (pintype "passive"))
      (node (ref "Q6") (pin "D2") (pinfunction "D_D2") (pintype "passive"))
      (node (ref "R4") (pin "2") (pinfunction "2_2") (pintype "passive"))
      (node (ref "SIM2-0512D_SIL7") (pin "1") (pinfunction "+VIN_1") (pintype "passive"))
      (node (ref "VCC") (pin "TP") (pinfunction "TP_TP") (pintype "input"))
    )
    (net (code "60") (name "unconnected-(IC1-PB1(OC1A)-Pad15)") (class "Default")
      (node (ref "IC1") (pin "15") (pinfunction "PB1(OC1A)_15") (pintype "bidirectional"))
    )
    (net (code "61") (name "unconnected-(IC1-PB2(SS{slash}OC1B)-Pad16)") (class "Default")
      (node (ref "IC1") (pin "16") (pinfunction "PB2(SS/OC1B)_16") (pintype "bidirectional"))
    )
    (net (code "62") (name "unconnected-(IC1-PC1(ADC1)-Pad24)") (class "Default")
      (node (ref "IC1") (pin "24") (pinfunction "PC1(ADC1)_24") (pintype "bidirectional"))
    )
    (net (code "63") (name "unconnected-(IC1-PC2(ADC2)-Pad25)") (class "Default")
      (node (ref "IC1") (pin "25") (pinfunction "PC2(ADC2)_25") (pintype "bidirectional"))
    )
    (net (code "64") (name "unconnected-(IC1-PC3(ADC3)-Pad26)") (class "Default")
      (node (ref "IC1") (pin "26") (pinfunction "PC3(ADC3)_26") (pintype "bidirectional"))
    )
    (net (code "65") (name "unconnected-(IC1-PC4(ADC4{slash}SDA)-Pad27)") (class "Default")
      (node (ref "IC1") (pin "27") (pinfunction "PC4(ADC4/SDA)_27") (pintype "bidirectional"))
    )
    (net (code "66") (name "unconnected-(IC1-PC5(ADC5{slash}SCL)-Pad28)") (class "Default")
      (node (ref "IC1") (pin "28") (pinfunction "PC5(ADC5/SCL)_28") (pintype "bidirectional"))
    )
    (net (code "67") (name "unconnected-(IC1-PD2(INT0)-Pad4)") (class "Default")
      (node (ref "IC1") (pin "4") (pinfunction "PD2(INT0)_4") (pintype "bidirectional"))
    )
    (net (code "68") (name "unconnected-(IC1-PD3(INT1)-Pad5)") (class "Default")
      (node (ref "IC1") (pin "5") (pinfunction "PD3(INT1)_5") (pintype "bidirectional"))
    )
    (net (code "69") (name "unconnected-(IC1-PD4(XCK{slash}T0)-Pad6)") (class "Default")
      (node (ref "IC1") (pin "6") (pinfunction "PD4(XCK/T0)_6") (pintype "bidirectional"))
    )
    (net (code "70") (name "unconnected-(IC1-PD5(T1)-Pad11)") (class "Default")
      (node (ref "IC1") (pin "11") (pinfunction "PD5(T1)_11") (pintype "bidirectional"))
    )
    (net (code "71") (name "unconnected-(IC2-CBUS0-Pad20)") (class "Default")
      (node (ref "IC2") (pin "20") (pinfunction "CBUS0_20") (pintype "bidirectional"))
    )
    (net (code "72") (name "unconnected-(IC2-CBUS1-Pad19)") (class "Default")
      (node (ref "IC2") (pin "19") (pinfunction "CBUS1_19") (pintype "bidirectional"))
    )
    (net (code "73") (name "unconnected-(IC2-CBUS2-Pad11)") (class "Default")
      (node (ref "IC2") (pin "11") (pinfunction "CBUS2_11") (pintype "bidirectional"))
    )
    (net (code "74") (name "unconnected-(IC2-CBUS4-Pad10)") (class "Default")
      (node (ref "IC2") (pin "10") (pinfunction "CBUS4_10") (pintype "bidirectional"))
    )
    (net (code "75") (name "unconnected-(IC2-OSCI-Pad23)") (class "Default")
      (node (ref "IC2") (pin "23") (pinfunction "OSCI_23") (pintype "input"))
    )
    (net (code "76") (name "unconnected-(IC2-OSCO-Pad24)") (class "Default")
      (node (ref "IC2") (pin "24") (pinfunction "OSCO_24") (pintype "output"))
    )
    (net (code "77") (name "unconnected-(IC2-_CTS-Pad9)") (class "Default")
      (node (ref "IC2") (pin "9") (pinfunction "_CTS_9") (pintype "input"))
    )
    (net (code "78") (name "unconnected-(IC2-_DCD-Pad8)") (class "Default")
      (node (ref "IC2") (pin "8") (pinfunction "_DCD_8") (pintype "input"))
    )
    (net (code "79") (name "unconnected-(IC2-_DSR-Pad7)") (class "Default")
      (node (ref "IC2") (pin "7") (pinfunction "_DSR_7") (pintype "input"))
    )
    (net (code "80") (name "unconnected-(IC2-_DTR-Pad2)") (class "Default")
      (node (ref "IC2") (pin "2") (pinfunction "_DTR_2") (pintype "input"))
    )
    (net (code "81") (name "unconnected-(IC2-_RI-Pad6)") (class "Default")
      (node (ref "IC2") (pin "6") (pinfunction "_RI_6") (pintype "input"))
    )
    (net (code "82") (name "unconnected-(IC2-_RTS-Pad3)") (class "Default")
      (node (ref "IC2") (pin "3") (pinfunction "_RTS_3") (pintype "output"))
    )
  )
)
